# SimpleEXGCircuit.net
KiCad netlist of a schematic drawn in EAGLE
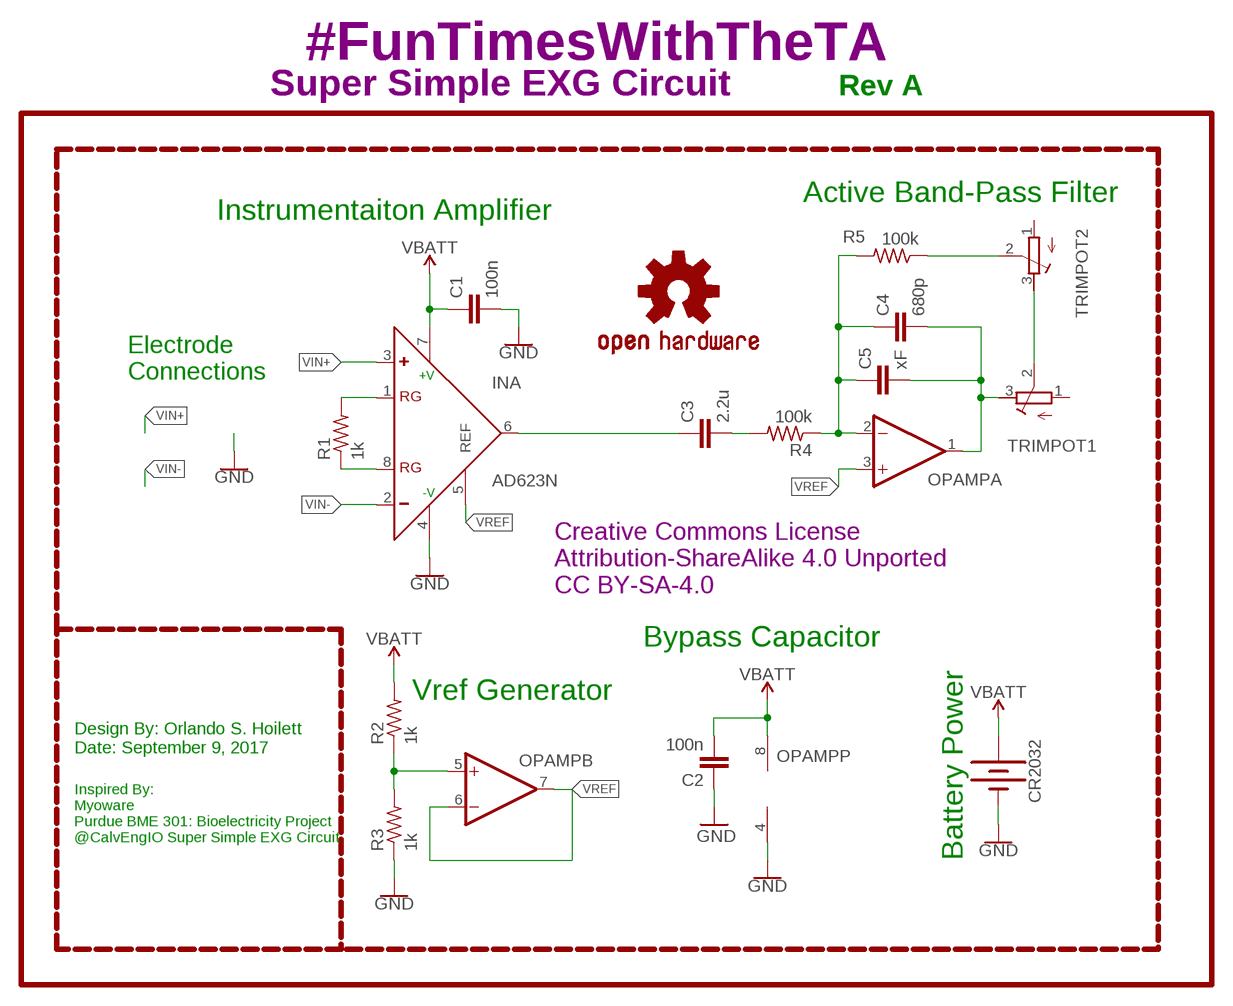
[diagram p0: schematic, sheet 1]

(export (version "E")
  (design (tool "Eeschema 10.0.6"))
  (components
    (comp (ref "C1")
      (value "100n")
      (footprint "eagle-import:C050-030X075")
      (libsource (lib "eagle-import") (part "CAPACITORC050-030X075"))
    )
    (comp (ref "C2")
      (value "100n")
      (footprint "eagle-import:C050-030X075")
      (libsource (lib "eagle-import") (part "CAPACITORC050-030X075"))
    )
    (comp (ref "C3")
      (value "2.2u")
      (footprint "eagle-import:C050-030X075")
      (libsource (lib "eagle-import") (part "CAPACITORC050-030X075"))
    )
    (comp (ref "C4")
      (value "680p")
      (footprint "eagle-import:C050-030X075")
      (libsource (lib "eagle-import") (part "CAPACITORC050-030X075"))
    )
    (comp (ref "C5")
      (value "xF")
      (footprint "eagle-import:C050-030X075")
      (libsource (lib "eagle-import") (part "CAPACITORC050-030X075"))
    )
    (comp (ref "CR2032")
      (value "BATTERY-20MM_SMD_4LEGS_OVERPASTE")
      (footprint "eagle-import:BATTCON_20MM_4LEGS_OVERPASTE")
      (libsource (lib "eagle-import") (part "BATTERY-20MM_SMD_4LEGS_OVERPASTE"))
    )
    (comp (ref "INA")
      (value "AD623N")
      (footprint "eagle-import:DIL08")
      (fields (field (name "MF") "ALTERA CORPORATION") (field (name "MPN") "AD623ANZ"))
      (libsource (lib "eagle-import") (part "AD623N"))
    )
    (comp (ref "LOGO1")
      (value "OSHW-LOGOS")
      (footprint "eagle-import:OSHW-LOGO-S")
      (libsource (lib "eagle-import") (part "OSHW-LOGOS"))
    )
    (comp (ref "OPAMP")
      (value "OP-DUALDIP08")
      (footprint "eagle-import:DIL08")
      (libsource (lib "eagle-import") (part "OP-DUALDIP08"))
    )
    (comp (ref "R1")
      (value "1k")
      (footprint "eagle-import:0207_10")
      (libsource (lib "eagle-import") (part "RESISTOR0207/10"))
    )
    (comp (ref "R2")
      (value "1k")
      (footprint "eagle-import:0207_10")
      (libsource (lib "eagle-import") (part "RESISTOR0207/10"))
    )
    (comp (ref "R3")
      (value "1k")
      (footprint "eagle-import:0207_10")
      (libsource (lib "eagle-import") (part "RESISTOR0207/10"))
    )
    (comp (ref "R4")
      (value "100k")
      (footprint "eagle-import:0207_10")
      (libsource (lib "eagle-import") (part "RESISTOR0207/10"))
    )
    (comp (ref "R5")
      (value "100k")
      (footprint "eagle-import:0207_10")
      (libsource (lib "eagle-import") (part "RESISTOR0207/10"))
    )
    (comp (ref "TRIMPOT1")
      (value "TRIM-POT-P160")
      (footprint "eagle-import:16MMROTARYPOT")
      (libsource (lib "eagle-import") (part "TRIM-POT-P160"))
    )
    (comp (ref "TRIMPOT2")
      (value "TRIM-POT-P160")
      (footprint "eagle-import:16MMROTARYPOT")
      (libsource (lib "eagle-import") (part "TRIM-POT-P160"))
    )
  )
  (nets
    (net (code "1") (name "GND") (class "Default")
      (node (ref "C1") (pin "2") (pinfunction "2_2") (pintype "passive"))
      (node (ref "C2") (pin "1") (pinfunction "1_1") (pintype "passive"))
      (node (ref "CR2032") (pin "2") (pinfunction "-_2") (pintype "power_in"))
      (node (ref "INA") (pin "4") (pinfunction "-V_4") (pintype "power_in"))
      (node (ref "OPAMP") (pin "4") (pinfunction "V-_4") (pintype "power_in"))
      (node (ref "R3") (pin "1") (pinfunction "1_1") (pintype "passive"))
    )
    (net (code "2") (name "Net-(C3-Pad2)") (class "Default")
      (node (ref "C3") (pin "2") (pinfunction "2_2") (pintype "passive"))
      (node (ref "R4") (pin "2") (pinfunction "2_2") (pintype "passive"))
    )
    (net (code "3") (name "Net-(INA-OUT)") (class "Default")
      (node (ref "C3") (pin "1") (pinfunction "1_1") (pintype "passive"))
      (node (ref "INA") (pin "6") (pinfunction "OUT_6") (pintype "output"))
    )
    (net (code "4") (name "Net-(INA-RG-Pad1)") (class "Default")
      (node (ref "INA") (pin "1") (pinfunction "RG_1") (pintype "passive"))
      (node (ref "R1") (pin "2") (pinfunction "2_2") (pintype "passive"))
    )
    (net (code "5") (name "Net-(INA-RG-Pad8)") (class "Default")
      (node (ref "INA") (pin "8") (pinfunction "RG_8") (pintype "passive"))
      (node (ref "R1") (pin "1") (pinfunction "1_1") (pintype "passive"))
    )
    (net (code "6") (name "Net-(OPAMPA--IN)") (class "Default")
      (node (ref "C4") (pin "1") (pinfunction "1_1") (pintype "passive"))
      (node (ref "C5") (pin "1") (pinfunction "1_1") (pintype "passive"))
      (node (ref "OPAMP") (pin "2") (pinfunction "-IN_2") (pintype "input"))
      (node (ref "R4") (pin "1") (pinfunction "1_1") (pintype "passive"))
      (node (ref "R5") (pin "2") (pinfunction "2_2") (pintype "passive"))
    )
    (net (code "7") (name "Net-(OPAMPA-OUT)") (class "Default")
      (node (ref "C4") (pin "2") (pinfunction "2_2") (pintype "passive"))
      (node (ref "C5") (pin "2") (pinfunction "2_2") (pintype "passive"))
      (node (ref "OPAMP") (pin "1") (pinfunction "OUT_1") (pintype "output"))
      (node (ref "TRIMPOT1") (pin "3") (pinfunction "E_3") (pintype "passive"))
    )
    (net (code "8") (name "Net-(OPAMPB-+IN)") (class "Default")
      (node (ref "OPAMP") (pin "5") (pinfunction "+IN_5") (pintype "input"))
      (node (ref "R2") (pin "1") (pinfunction "1_1") (pintype "passive"))
      (node (ref "R3") (pin "2") (pinfunction "2_2") (pintype "passive"))
    )
    (net (code "9") (name "Net-(TRIMPOT1-S)") (class "Default")
      (node (ref "TRIMPOT1") (pin "2") (pinfunction "S_2") (pintype "passive"))
      (node (ref "TRIMPOT2") (pin "3") (pinfunction "E_3") (pintype "passive"))
    )
    (net (code "10") (name "Net-(TRIMPOT2-S)") (class "Default")
      (node (ref "R5") (pin "1") (pinfunction "1_1") (pintype "passive"))
      (node (ref "TRIMPOT2") (pin "2") (pinfunction "S_2") (pintype "passive"))
    )
    (net (code "11") (name "VBATT") (class "Default")
      (node (ref "C1") (pin "1") (pinfunction "1_1") (pintype "passive"))
      (node (ref "C2") (pin "2") (pinfunction "2_2") (pintype "passive"))
      (node (ref "CR2032") (pin "1") (pinfunction "+_1") (pintype "power_in"))
      (node (ref "INA") (pin "7") (pinfunction "+V_7") (pintype "power_in"))
      (node (ref "OPAMP") (pin "8") (pinfunction "V+_8") (pintype "power_in"))
      (node (ref "R2") (pin "2") (pinfunction "2_2") (pintype "passive"))
    )
    (net (code "12") (name "VIN+") (class "Default")
      (node (ref "INA") (pin "3") (pinfunction "+_3") (pintype "input"))
    )
    (net (code "13") (name "VIN-") (class "Default")
      (node (ref "INA") (pin "2") (pinfunction "-_2") (pintype "input"))
    )
    (net (code "14") (name "VREF") (class "Default")
      (node (ref "INA") (pin "5") (pinfunction "REF_5") (pintype "passive"))
      (node (ref "OPAMP") (pin "3") (pinfunction "+IN_3") (pintype "input"))
      (node (ref "OPAMP") (pin "6") (pinfunction "-IN_6") (pintype "input"))
      (node (ref "OPAMP") (pin "7") (pinfunction "OUT_7") (pintype "output"))
    )
    (net (code "15") (name "unconnected-(TRIMPOT1-A-Pad1)") (class "Default")
      (node (ref "TRIMPOT1") (pin "1") (pinfunction "A_1") (pintype "passive"))
    )
    (net (code "16") (name "unconnected-(TRIMPOT2-A-Pad1)") (class "Default")
      (node (ref "TRIMPOT2") (pin "1") (pinfunction "A_1") (pintype "passive"))
    )
  )
)
